# ProDocument_N64_SpyDVI_QSB_2024-08-21.net
KiCad netlist of a schematic drawn in EasyEDA Pro
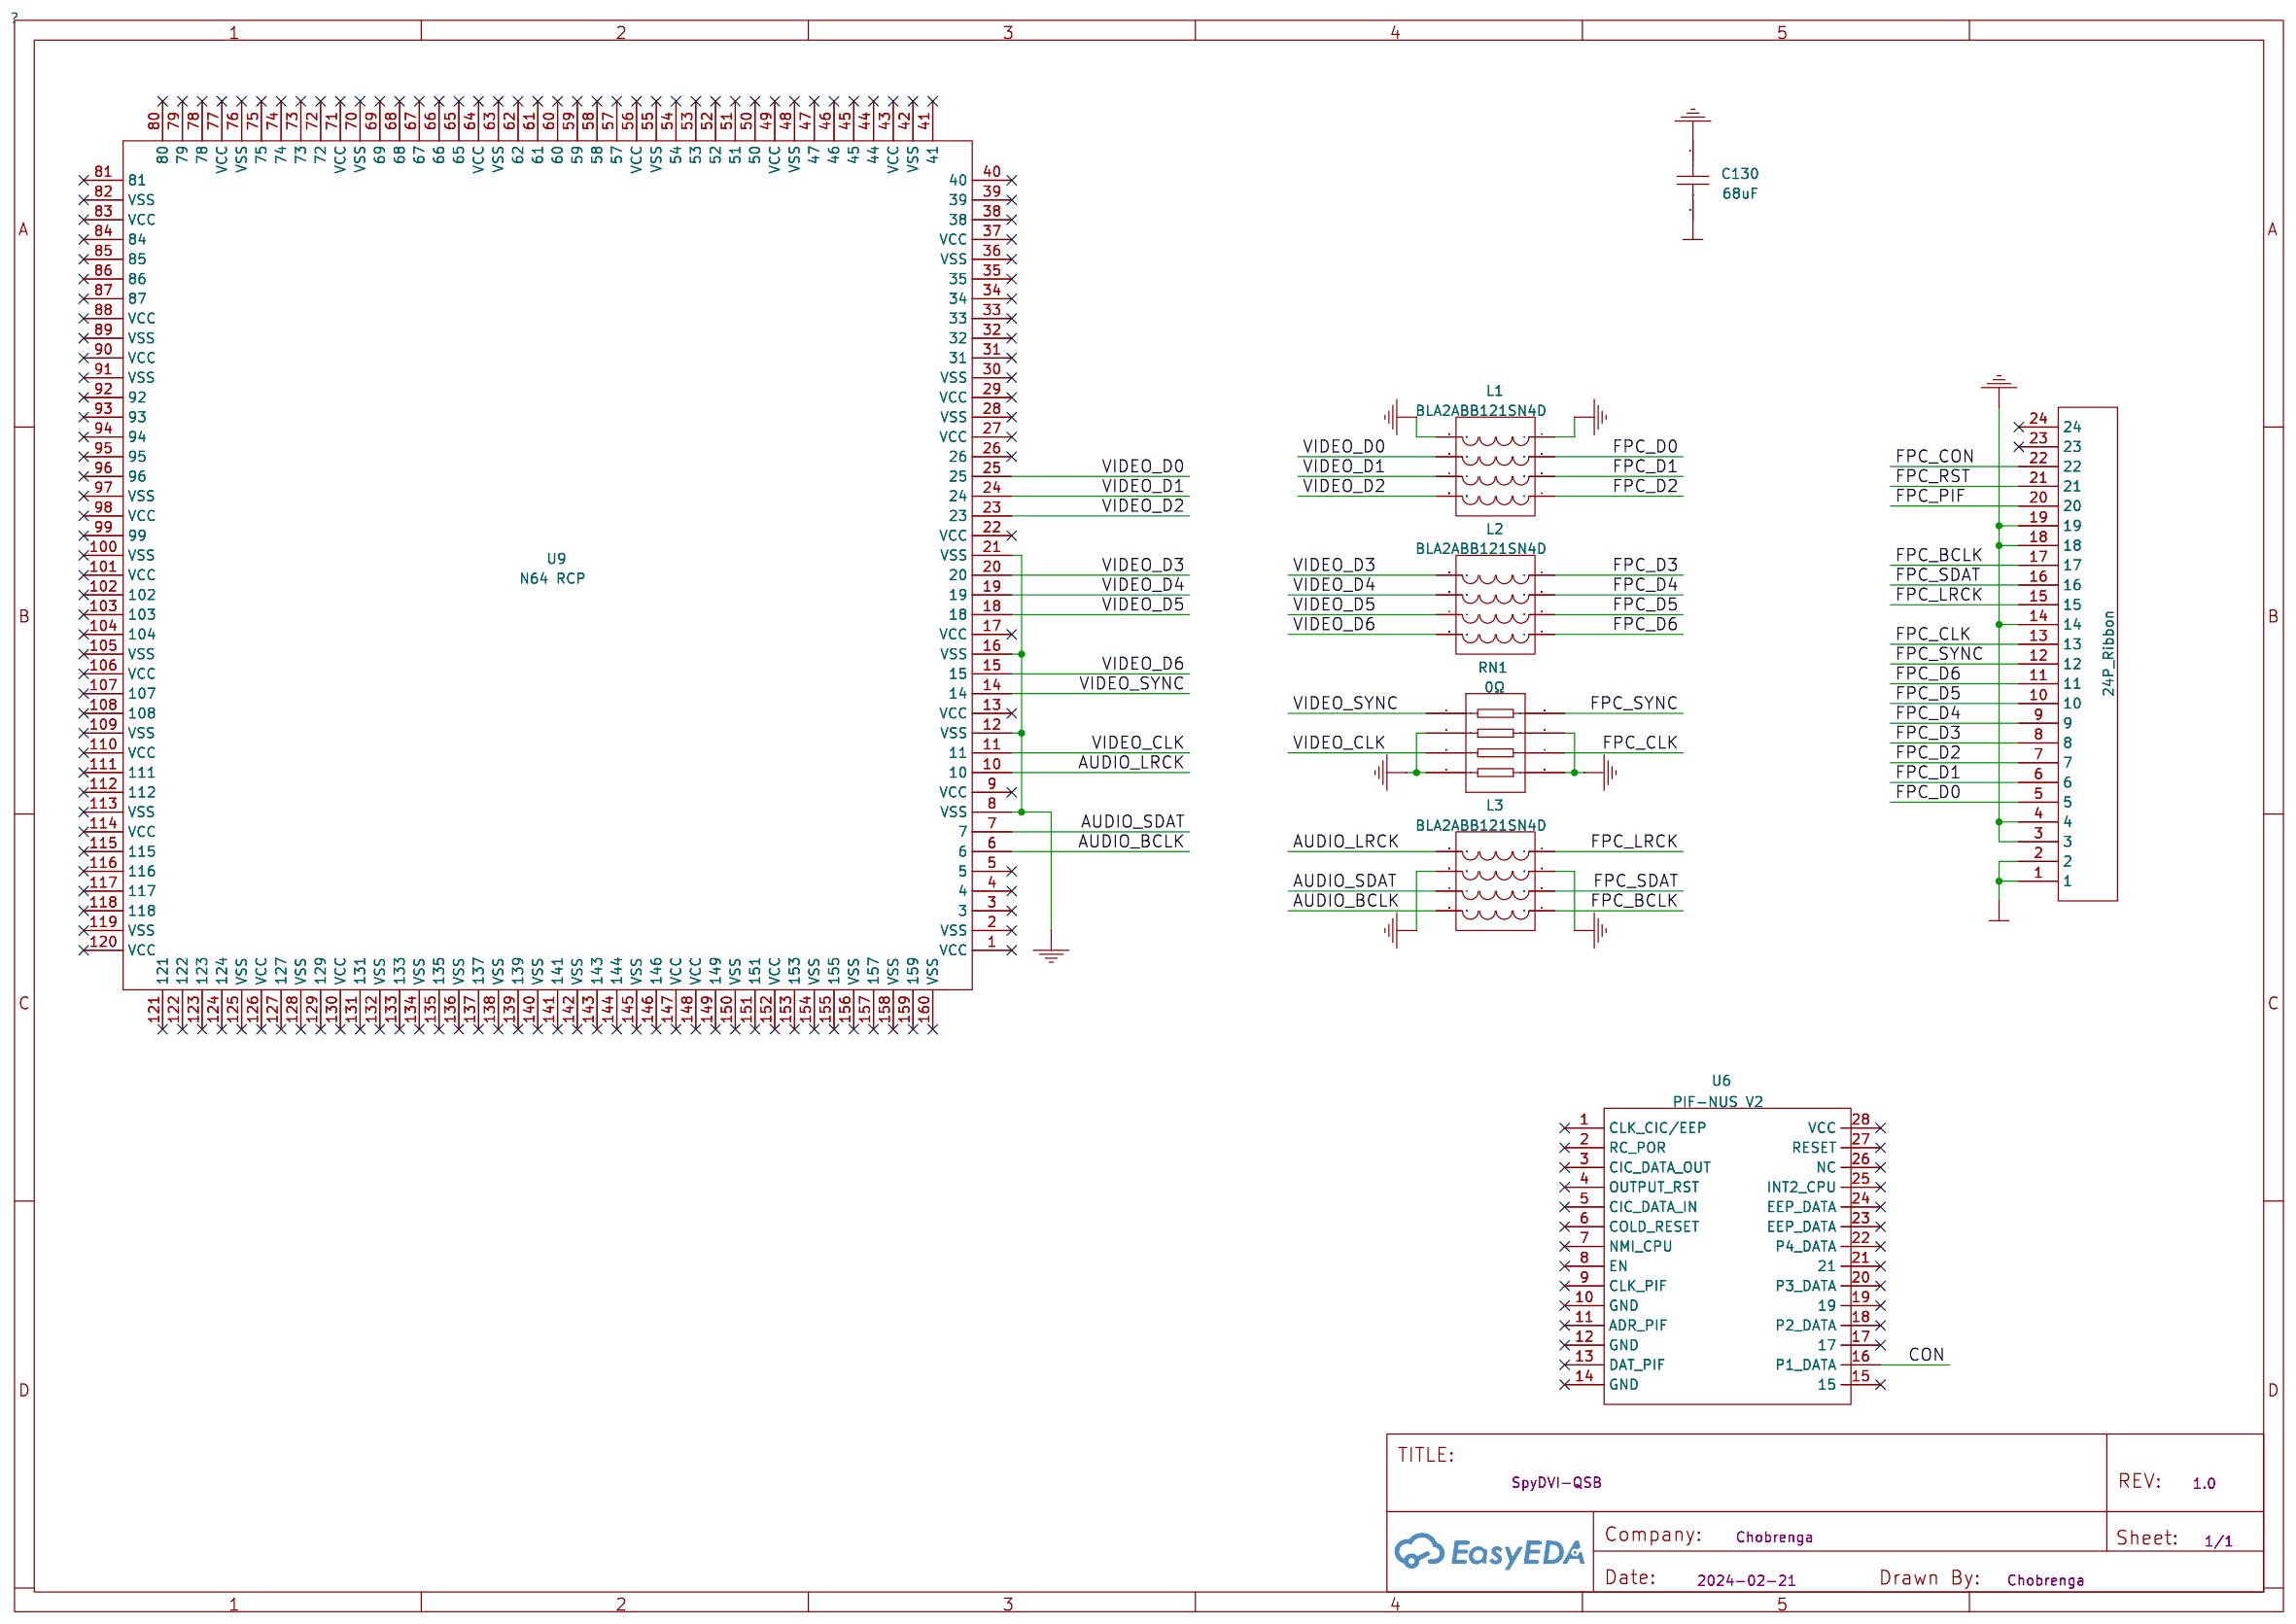
[diagram p0: schematic sheet]

(export (version "E")
  (design (tool "Eeschema 10.0.6"))
  (components
    (comp (ref "C130") (value "68uF") (libsource (lib "easyedapro") (part "68uF")))
    (comp (ref "L1")
      (value "BLA2ABB121SN4D")
      (footprint "easyedapro:BEAD-SMD_8P-L2.0-W1.0-P0.50-TL")
      (fields (field (name "Manufacturer") "muRata(村田)"))
      (libsource (lib "easyedapro") (part "BLA2ABB121SN4D"))
    )
    (comp (ref "L2")
      (value "BLA2ABB121SN4D")
      (footprint "easyedapro:BEAD-SMD_8P-L2.0-W1.0-P0.50-TL")
      (fields (field (name "Manufacturer") "muRata(村田)"))
      (libsource (lib "easyedapro") (part "BLA2ABB121SN4D"))
    )
    (comp (ref "L3")
      (value "BLA2ABB121SN4D")
      (footprint "easyedapro:BEAD-SMD_8P-L2.0-W1.0-P0.50-TL")
      (fields (field (name "Manufacturer") "muRata(村田)"))
      (libsource (lib "easyedapro") (part "BLA2ABB121SN4D"))
    )
    (comp (ref "RN1")
      (value "0Ω")
      (footprint "easyedapro:RES-ARRAY-SMD_0402-8P-L2.0-W1.0-BL")
      (fields (field (name "Manufacturer Part") "RC-MT08W000JT") (field (name "Manufacturer") "FH(风华)"))
      (libsource (lib "easyedapro") (part "0Ω"))
    )
    (comp (ref "U1")
      (value "24P_Ribbon")
      (footprint "easyedapro:24P_FFC")
      (libsource (lib "easyedapro") (part "24P_Ribbon"))
    )
    (comp (ref "U6") (value "PIF-NUS V2") (libsource (lib "easyedapro") (part "PIF-NUS V2")))
    (comp (ref "U9")
      (value "N64 RCP")
      (footprint "easyedapro:RCP NUS")
      (libsource (lib "easyedapro") (part "N64 RCP"))
    )
  )
  (nets
    (net (code "1") (name "+5V") (class "Default")
      (node (ref "C130") (pin "2") (pinfunction "2_2") (pintype "unspecified"))
      (node (ref "U1") (pin "1") (pinfunction "1_1") (pintype "unspecified"))
      (node (ref "U1") (pin "2") (pinfunction "2_2") (pintype "unspecified"))
    )
    (net (code "2") (name "/AUDIO_BCLK") (class "Default")
      (node (ref "L3") (pin "8") (pinfunction "8_8") (pintype "unspecified"))
      (node (ref "U9") (pin "6") (pinfunction "6_6") (pintype "unspecified"))
    )
    (net (code "3") (name "/AUDIO_LRCK") (class "Default")
      (node (ref "L3") (pin "5") (pinfunction "5_5") (pintype "unspecified"))
      (node (ref "U9") (pin "10") (pinfunction "10_10") (pintype "unspecified"))
    )
    (net (code "4") (name "/AUDIO_SDAT") (class "Default")
      (node (ref "L3") (pin "7") (pinfunction "7_7") (pintype "unspecified"))
      (node (ref "U9") (pin "7") (pinfunction "7_7") (pintype "unspecified"))
    )
    (net (code "5") (name "/CON") (class "Default")
      (node (ref "U6") (pin "16") (pinfunction "P1_DATA_16") (pintype "unspecified"))
    )
    (net (code "6") (name "/FPC_BCLK") (class "Default")
      (node (ref "L3") (pin "1") (pinfunction "1_1") (pintype "unspecified"))
      (node (ref "U1") (pin "17") (pinfunction "17_17") (pintype "unspecified"))
    )
    (net (code "7") (name "/FPC_CLK") (class "Default")
      (node (ref "RN1") (pin "7") (pinfunction "7_7") (pintype "input"))
      (node (ref "U1") (pin "13") (pinfunction "13_13") (pintype "unspecified"))
    )
    (net (code "8") (name "/FPC_CON") (class "Default")
      (node (ref "U1") (pin "22") (pinfunction "22_22") (pintype "unspecified"))
    )
    (net (code "9") (name "/FPC_D0") (class "Default")
      (node (ref "L1") (pin "3") (pinfunction "3_3") (pintype "unspecified"))
      (node (ref "U1") (pin "5") (pinfunction "5_5") (pintype "unspecified"))
    )
    (net (code "10") (name "/FPC_D1") (class "Default")
      (node (ref "L1") (pin "2") (pinfunction "2_2") (pintype "unspecified"))
      (node (ref "U1") (pin "6") (pinfunction "6_6") (pintype "unspecified"))
    )
    (net (code "11") (name "/FPC_D2") (class "Default")
      (node (ref "L1") (pin "1") (pinfunction "1_1") (pintype "unspecified"))
      (node (ref "U1") (pin "7") (pinfunction "7_7") (pintype "unspecified"))
    )
    (net (code "12") (name "/FPC_D3") (class "Default")
      (node (ref "L2") (pin "4") (pinfunction "4_4") (pintype "unspecified"))
      (node (ref "U1") (pin "8") (pinfunction "8_8") (pintype "unspecified"))
    )
    (net (code "13") (name "/FPC_D4") (class "Default")
      (node (ref "L2") (pin "3") (pinfunction "3_3") (pintype "unspecified"))
      (node (ref "U1") (pin "9") (pinfunction "9_9") (pintype "unspecified"))
    )
    (net (code "14") (name "/FPC_D5") (class "Default")
      (node (ref "L2") (pin "2") (pinfunction "2_2") (pintype "unspecified"))
      (node (ref "U1") (pin "10") (pinfunction "10_10") (pintype "unspecified"))
    )
    (net (code "15") (name "/FPC_D6") (class "Default")
      (node (ref "L2") (pin "1") (pinfunction "1_1") (pintype "unspecified"))
      (node (ref "U1") (pin "11") (pinfunction "11_11") (pintype "unspecified"))
    )
    (net (code "16") (name "/FPC_LRCK") (class "Default")
      (node (ref "L3") (pin "4") (pinfunction "4_4") (pintype "unspecified"))
      (node (ref "U1") (pin "15") (pinfunction "15_15") (pintype "unspecified"))
    )
    (net (code "17") (name "/FPC_PIF") (class "Default")
      (node (ref "U1") (pin "20") (pinfunction "20_20") (pintype "unspecified"))
    )
    (net (code "18") (name "/FPC_RST") (class "Default")
      (node (ref "U1") (pin "21") (pinfunction "21_21") (pintype "unspecified"))
    )
    (net (code "19") (name "/FPC_SDAT") (class "Default")
      (node (ref "L3") (pin "2") (pinfunction "2_2") (pintype "unspecified"))
      (node (ref "U1") (pin "16") (pinfunction "16_16") (pintype "unspecified"))
    )
    (net (code "20") (name "/FPC_SYNC") (class "Default")
      (node (ref "RN1") (pin "5") (pinfunction "5_5") (pintype "input"))
      (node (ref "U1") (pin "12") (pinfunction "12_12") (pintype "unspecified"))
    )
    (net (code "21") (name "/VIDEO_CLK") (class "Default")
      (node (ref "RN1") (pin "2") (pinfunction "2_2") (pintype "input"))
      (node (ref "U9") (pin "11") (pinfunction "11_11") (pintype "unspecified"))
    )
    (net (code "22") (name "/VIDEO_D0") (class "Default")
      (node (ref "L1") (pin "6") (pinfunction "6_6") (pintype "unspecified"))
      (node (ref "U9") (pin "25") (pinfunction "25_25") (pintype "unspecified"))
    )
    (net (code "23") (name "/VIDEO_D1") (class "Default")
      (node (ref "L1") (pin "7") (pinfunction "7_7") (pintype "unspecified"))
      (node (ref "U9") (pin "24") (pinfunction "24_24") (pintype "unspecified"))
    )
    (net (code "24") (name "/VIDEO_D2") (class "Default")
      (node (ref "L1") (pin "8") (pinfunction "8_8") (pintype "unspecified"))
      (node (ref "U9") (pin "23") (pinfunction "23_23") (pintype "unspecified"))
    )
    (net (code "25") (name "/VIDEO_D3") (class "Default")
      (node (ref "L2") (pin "5") (pinfunction "5_5") (pintype "unspecified"))
      (node (ref "U9") (pin "20") (pinfunction "20_20") (pintype "unspecified"))
    )
    (net (code "26") (name "/VIDEO_D4") (class "Default")
      (node (ref "L2") (pin "6") (pinfunction "6_6") (pintype "unspecified"))
      (node (ref "U9") (pin "19") (pinfunction "19_19") (pintype "unspecified"))
    )
    (net (code "27") (name "/VIDEO_D5") (class "Default")
      (node (ref "L2") (pin "7") (pinfunction "7_7") (pintype "unspecified"))
      (node (ref "U9") (pin "18") (pinfunction "18_18") (pintype "unspecified"))
    )
    (net (code "28") (name "/VIDEO_D6") (class "Default")
      (node (ref "L2") (pin "8") (pinfunction "8_8") (pintype "unspecified"))
      (node (ref "U9") (pin "15") (pinfunction "15_15") (pintype "unspecified"))
    )
    (net (code "29") (name "/VIDEO_SYNC") (class "Default")
      (node (ref "RN1") (pin "4") (pinfunction "4_4") (pintype "input"))
      (node (ref "U9") (pin "14") (pinfunction "14_14") (pintype "unspecified"))
    )
    (net (code "30") (name "GND") (class "Default")
      (node (ref "C130") (pin "1") (pinfunction "1_1") (pintype "unspecified"))
      (node (ref "L1") (pin "4") (pinfunction "4_4") (pintype "unspecified"))
      (node (ref "L1") (pin "5") (pinfunction "5_5") (pintype "unspecified"))
      (node (ref "L3") (pin "3") (pinfunction "3_3") (pintype "unspecified"))
      (node (ref "L3") (pin "6") (pinfunction "6_6") (pintype "unspecified"))
      (node (ref "RN1") (pin "1") (pinfunction "1_1") (pintype "input"))
      (node (ref "RN1") (pin "3") (pinfunction "3_3") (pintype "input"))
      (node (ref "RN1") (pin "6") (pinfunction "6_6") (pintype "input"))
      (node (ref "RN1") (pin "8") (pinfunction "8_8") (pintype "input"))
      (node (ref "U1") (pin "14") (pinfunction "14_14") (pintype "unspecified"))
      (node (ref "U1") (pin "18") (pinfunction "18_18") (pintype "unspecified"))
      (node (ref "U1") (pin "19") (pinfunction "19_19") (pintype "unspecified"))
      (node (ref "U1") (pin "3") (pinfunction "3_3") (pintype "unspecified"))
      (node (ref "U1") (pin "4") (pinfunction "4_4") (pintype "unspecified"))
      (node (ref "U9") (pin "12") (pinfunction "VSS_12") (pintype "unspecified"))
      (node (ref "U9") (pin "16") (pinfunction "VSS_16") (pintype "unspecified"))
      (node (ref "U9") (pin "21") (pinfunction "VSS_21") (pintype "unspecified"))
      (node (ref "U9") (pin "8") (pinfunction "VSS_8") (pintype "unspecified"))
    )
    (net (code "31") (name "unconnected-(U1-Pad23)") (class "Default")
      (node (ref "U1") (pin "23") (pinfunction "23_23") (pintype "unspecified+no_connect"))
    )
    (net (code "32") (name "unconnected-(U1-Pad24)") (class "Default")
      (node (ref "U1") (pin "24") (pinfunction "24_24") (pintype "unspecified+no_connect"))
    )
    (net (code "33") (name "unconnected-(U6-ADR_PIF-Pad11)") (class "Default")
      (node (ref "U6") (pin "11") (pinfunction "ADR_PIF_11") (pintype "unspecified+no_connect"))
    )
    (net (code "34") (name "unconnected-(U6-CIC_DATA_IN-Pad5)") (class "Default")
      (node (ref "U6") (pin "5") (pinfunction "CIC_DATA_IN_5") (pintype "unspecified+no_connect"))
    )
    (net (code "35") (name "unconnected-(U6-CIC_DATA_OUT-Pad3)") (class "Default")
      (node (ref "U6") (pin "3") (pinfunction "CIC_DATA_OUT_3") (pintype "unspecified+no_connect"))
    )
    (net (code "36") (name "unconnected-(U6-CLK_CIC{slash}EEP-Pad1)") (class "Default")
      (node (ref "U6") (pin "1") (pinfunction "CLK_CIC/EEP_1") (pintype "unspecified+no_connect"))
    )
    (net (code "37") (name "unconnected-(U6-CLK_PIF-Pad9)") (class "Default")
      (node (ref "U6") (pin "9") (pinfunction "CLK_PIF_9") (pintype "unspecified+no_connect"))
    )
    (net (code "38") (name "unconnected-(U6-COLD_RESET-Pad6)") (class "Default")
      (node (ref "U6") (pin "6") (pinfunction "COLD_RESET_6") (pintype "unspecified+no_connect"))
    )
    (net (code "39") (name "unconnected-(U6-DAT_PIF-Pad13)") (class "Default")
      (node (ref "U6") (pin "13") (pinfunction "DAT_PIF_13") (pintype "unspecified+no_connect"))
    )
    (net (code "40") (name "unconnected-(U6-EEP_DATA-Pad23)") (class "Default")
      (node (ref "U6") (pin "23") (pinfunction "EEP_DATA_23") (pintype "unspecified+no_connect"))
    )
    (net (code "41") (name "unconnected-(U6-EEP_DATA-Pad24)") (class "Default")
      (node (ref "U6") (pin "24") (pinfunction "EEP_DATA_24") (pintype "unspecified+no_connect"))
    )
    (net (code "42") (name "unconnected-(U6-EN-Pad8)") (class "Default")
      (node (ref "U6") (pin "8") (pinfunction "EN_8") (pintype "unspecified+no_connect"))
    )
    (net (code "43") (name "unconnected-(U6-GND-Pad10)") (class "Default")
      (node (ref "U6") (pin "10") (pinfunction "GND_10") (pintype "unspecified+no_connect"))
    )
    (net (code "44") (name "unconnected-(U6-GND-Pad12)") (class "Default")
      (node (ref "U6") (pin "12") (pinfunction "GND_12") (pintype "unspecified+no_connect"))
    )
    (net (code "45") (name "unconnected-(U6-GND-Pad14)") (class "Default")
      (node (ref "U6") (pin "14") (pinfunction "GND_14") (pintype "unspecified+no_connect"))
    )
    (net (code "46") (name "unconnected-(U6-INT2_CPU-Pad25)") (class "Default")
      (node (ref "U6") (pin "25") (pinfunction "INT2_CPU_25") (pintype "unspecified+no_connect"))
    )
    (net (code "47") (name "unconnected-(U6-NC-Pad26)") (class "Default")
      (node (ref "U6") (pin "26") (pinfunction "NC_26") (pintype "unspecified+no_connect"))
    )
    (net (code "48") (name "unconnected-(U6-NMI_CPU-Pad7)") (class "Default")
      (node (ref "U6") (pin "7") (pinfunction "NMI_CPU_7") (pintype "unspecified+no_connect"))
    )
    (net (code "49") (name "unconnected-(U6-OUTPUT_RST-Pad4)") (class "Default")
      (node (ref "U6") (pin "4") (pinfunction "OUTPUT_RST_4") (pintype "unspecified+no_connect"))
    )
    (net (code "50") (name "unconnected-(U6-P2_DATA-Pad18)") (class "Default")
      (node (ref "U6") (pin "18") (pinfunction "P2_DATA_18") (pintype "unspecified+no_connect"))
    )
    (net (code "51") (name "unconnected-(U6-P3_DATA-Pad20)") (class "Default")
      (node (ref "U6") (pin "20") (pinfunction "P3_DATA_20") (pintype "unspecified+no_connect"))
    )
    (net (code "52") (name "unconnected-(U6-P4_DATA-Pad22)") (class "Default")
      (node (ref "U6") (pin "22") (pinfunction "P4_DATA_22") (pintype "unspecified+no_connect"))
    )
    (net (code "53") (name "unconnected-(U6-Pad15)") (class "Default")
      (node (ref "U6") (pin "15") (pinfunction "15_15") (pintype "unspecified+no_connect"))
    )
    (net (code "54") (name "unconnected-(U6-Pad17)") (class "Default")
      (node (ref "U6") (pin "17") (pinfunction "17_17") (pintype "unspecified+no_connect"))
    )
    (net (code "55") (name "unconnected-(U6-Pad19)") (class "Default")
      (node (ref "U6") (pin "19") (pinfunction "19_19") (pintype "unspecified+no_connect"))
    )
    (net (code "56") (name "unconnected-(U6-Pad21)") (class "Default")
      (node (ref "U6") (pin "21") (pinfunction "21_21") (pintype "unspecified+no_connect"))
    )
    (net (code "57") (name "unconnected-(U6-RC_POR-Pad2)") (class "Default")
      (node (ref "U6") (pin "2") (pinfunction "RC_POR_2") (pintype "unspecified+no_connect"))
    )
    (net (code "58") (name "unconnected-(U6-RESET-Pad27)") (class "Default")
      (node (ref "U6") (pin "27") (pinfunction "RESET_27") (pintype "unspecified+no_connect"))
    )
    (net (code "59") (name "unconnected-(U6-VCC-Pad28)") (class "Default")
      (node (ref "U6") (pin "28") (pinfunction "VCC_28") (pintype "unspecified+no_connect"))
    )
    (net (code "60") (name "unconnected-(U9-Pad3)") (class "Default")
      (node (ref "U9") (pin "3") (pinfunction "3_3") (pintype "unspecified+no_connect"))
    )
    (net (code "61") (name "unconnected-(U9-Pad4)") (class "Default")
      (node (ref "U9") (pin "4") (pinfunction "4_4") (pintype "unspecified+no_connect"))
    )
    (net (code "62") (name "unconnected-(U9-Pad5)") (class "Default")
      (node (ref "U9") (pin "5") (pinfunction "5_5") (pintype "unspecified+no_connect"))
    )
    (net (code "63") (name "unconnected-(U9-Pad26)") (class "Default")
      (node (ref "U9") (pin "26") (pinfunction "26_26") (pintype "unspecified+no_connect"))
    )
    (net (code "64") (name "unconnected-(U9-Pad31)") (class "Default")
      (node (ref "U9") (pin "31") (pinfunction "31_31") (pintype "unspecified+no_connect"))
    )
    (net (code "65") (name "unconnected-(U9-Pad32)") (class "Default")
      (node (ref "U9") (pin "32") (pinfunction "32_32") (pintype "unspecified+no_connect"))
    )
    (net (code "66") (name "unconnected-(U9-Pad33)") (class "Default")
      (node (ref "U9") (pin "33") (pinfunction "33_33") (pintype "unspecified+no_connect"))
    )
    (net (code "67") (name "unconnected-(U9-Pad34)") (class "Default")
      (node (ref "U9") (pin "34") (pinfunction "34_34") (pintype "unspecified+no_connect"))
    )
    (net (code "68") (name "unconnected-(U9-Pad35)") (class "Default")
      (node (ref "U9") (pin "35") (pinfunction "35_35") (pintype "unspecified+no_connect"))
    )
    (net (code "69") (name "unconnected-(U9-Pad38)") (class "Default")
      (node (ref "U9") (pin "38") (pinfunction "38_38") (pintype "unspecified+no_connect"))
    )
    (net (code "70") (name "unconnected-(U9-Pad39)") (class "Default")
      (node (ref "U9") (pin "39") (pinfunction "39_39") (pintype "unspecified+no_connect"))
    )
    (net (code "71") (name "unconnected-(U9-Pad40)") (class "Default")
      (node (ref "U9") (pin "40") (pinfunction "40_40") (pintype "unspecified+no_connect"))
    )
    (net (code "72") (name "unconnected-(U9-Pad41)") (class "Default")
      (node (ref "U9") (pin "41") (pinfunction "41_41") (pintype "unspecified+no_connect"))
    )
    (net (code "73") (name "unconnected-(U9-Pad44)") (class "Default")
      (node (ref "U9") (pin "44") (pinfunction "44_44") (pintype "unspecified+no_connect"))
    )
    (net (code "74") (name "unconnected-(U9-Pad45)") (class "Default")
      (node (ref "U9") (pin "45") (pinfunction "45_45") (pintype "unspecified+no_connect"))
    )
    (net (code "75") (name "unconnected-(U9-Pad46)") (class "Default")
      (node (ref "U9") (pin "46") (pinfunction "46_46") (pintype "unspecified+no_connect"))
    )
    (net (code "76") (name "unconnected-(U9-Pad47)") (class "Default")
      (node (ref "U9") (pin "47") (pinfunction "47_47") (pintype "unspecified+no_connect"))
    )
    (net (code "77") (name "unconnected-(U9-Pad50)") (class "Default")
      (node (ref "U9") (pin "50") (pinfunction "50_50") (pintype "unspecified+no_connect"))
    )
    (net (code "78") (name "unconnected-(U9-Pad51)") (class "Default")
      (node (ref "U9") (pin "51") (pinfunction "51_51") (pintype "unspecified+no_connect"))
    )
    (net (code "79") (name "unconnected-(U9-Pad52)") (class "Default")
      (node (ref "U9") (pin "52") (pinfunction "52_52") (pintype "unspecified+no_connect"))
    )
    (net (code "80") (name "unconnected-(U9-Pad53)") (class "Default")
      (node (ref "U9") (pin "53") (pinfunction "53_53") (pintype "unspecified+no_connect"))
    )
    (net (code "81") (name "unconnected-(U9-Pad54)") (class "Default")
      (node (ref "U9") (pin "54") (pinfunction "54_54") (pintype "unspecified+no_connect"))
    )
    (net (code "82") (name "unconnected-(U9-Pad57)") (class "Default")
      (node (ref "U9") (pin "57") (pinfunction "57_57") (pintype "unspecified+no_connect"))
    )
    (net (code "83") (name "unconnected-(U9-Pad58)") (class "Default")
      (node (ref "U9") (pin "58") (pinfunction "58_58") (pintype "unspecified+no_connect"))
    )
    (net (code "84") (name "unconnected-(U9-Pad59)") (class "Default")
      (node (ref "U9") (pin "59") (pinfunction "59_59") (pintype "unspecified+no_connect"))
    )
    (net (code "85") (name "unconnected-(U9-Pad60)") (class "Default")
      (node (ref "U9") (pin "60") (pinfunction "60_60") (pintype "unspecified+no_connect"))
    )
    (net (code "86") (name "unconnected-(U9-Pad61)") (class "Default")
      (node (ref "U9") (pin "61") (pinfunction "61_61") (pintype "unspecified+no_connect"))
    )
    (net (code "87") (name "unconnected-(U9-Pad62)") (class "Default")
      (node (ref "U9") (pin "62") (pinfunction "62_62") (pintype "unspecified+no_connect"))
    )
    (net (code "88") (name "unconnected-(U9-Pad65)") (class "Default")
      (node (ref "U9") (pin "65") (pinfunction "65_65") (pintype "unspecified+no_connect"))
    )
    (net (code "89") (name "unconnected-(U9-Pad66)") (class "Default")
      (node (ref "U9") (pin "66") (pinfunction "66_66") (pintype "unspecified+no_connect"))
    )
    (net (code "90") (name "unconnected-(U9-Pad67)") (class "Default")
      (node (ref "U9") (pin "67") (pinfunction "67_67") (pintype "unspecified+no_connect"))
    )
    (net (code "91") (name "unconnected-(U9-Pad68)") (class "Default")
      (node (ref "U9") (pin "68") (pinfunction "68_68") (pintype "unspecified+no_connect"))
    )
    (net (code "92") (name "unconnected-(U9-Pad69)") (class "Default")
      (node (ref "U9") (pin "69") (pinfunction "69_69") (pintype "unspecified+no_connect"))
    )
    (net (code "93") (name "unconnected-(U9-Pad72)") (class "Default")
      (node (ref "U9") (pin "72") (pinfunction "72_72") (pintype "unspecified+no_connect"))
    )
    (net (code "94") (name "unconnected-(U9-Pad73)") (class "Default")
      (node (ref "U9") (pin "73") (pinfunction "73_73") (pintype "unspecified+no_connect"))
    )
    (net (code "95") (name "unconnected-(U9-Pad74)") (class "Default")
      (node (ref "U9") (pin "74") (pinfunction "74_74") (pintype "unspecified+no_connect"))
    )
    (net (code "96") (name "unconnected-(U9-Pad75)") (class "Default")
      (node (ref "U9") (pin "75") (pinfunction "75_75") (pintype "unspecified+no_connect"))
    )
    (net (code "97") (name "unconnected-(U9-Pad78)") (class "Default")
      (node (ref "U9") (pin "78") (pinfunction "78_78") (pintype "unspecified+no_connect"))
    )
    (net (code "98") (name "unconnected-(U9-Pad79)") (class "Default")
      (node (ref "U9") (pin "79") (pinfunction "79_79") (pintype "unspecified+no_connect"))
    )
    (net (code "99") (name "unconnected-(U9-Pad80)") (class "Default")
      (node (ref "U9") (pin "80") (pinfunction "80_80") (pintype "unspecified+no_connect"))
    )
    (net (code "100") (name "unconnected-(U9-Pad81)") (class "Default")
      (node (ref "U9") (pin "81") (pinfunction "81_81") (pintype "unspecified+no_connect"))
    )
    (net (code "101") (name "unconnected-(U9-Pad84)") (class "Default")
      (node (ref "U9") (pin "84") (pinfunction "84_84") (pintype "unspecified+no_connect"))
    )
    (net (code "102") (name "unconnected-(U9-Pad85)") (class "Default")
      (node (ref "U9") (pin "85") (pinfunction "85_85") (pintype "unspecified+no_connect"))
    )
    (net (code "103") (name "unconnected-(U9-Pad86)") (class "Default")
      (node (ref "U9") (pin "86") (pinfunction "86_86") (pintype "unspecified+no_connect"))
    )
    (net (code "104") (name "unconnected-(U9-Pad87)") (class "Default")
      (node (ref "U9") (pin "87") (pinfunction "87_87") (pintype "unspecified+no_connect"))
    )
    (net (code "105") (name "unconnected-(U9-Pad92)") (class "Default")
      (node (ref "U9") (pin "92") (pinfunction "92_92") (pintype "unspecified+no_connect"))
    )
    (net (code "106") (name "unconnected-(U9-Pad93)") (class "Default")
      (node (ref "U9") (pin "93") (pinfunction "93_93") (pintype "unspecified+no_connect"))
    )
    (net (code "107") (name "unconnected-(U9-Pad94)") (class "Default")
      (node (ref "U9") (pin "94") (pinfunction "94_94") (pintype "unspecified+no_connect"))
    )
    (net (code "108") (name "unconnected-(U9-Pad95)") (class "Default")
      (node (ref "U9") (pin "95") (pinfunction "95_95") (pintype "unspecified+no_connect"))
    )
    (net (code "109") (name "unconnected-(U9-Pad96)") (class "Default")
      (node (ref "U9") (pin "96") (pinfunction "96_96") (pintype "unspecified+no_connect"))
    )
    (net (code "110") (name "unconnected-(U9-Pad99)") (class "Default")
      (node (ref "U9") (pin "99") (pinfunction "99_99") (pintype "unspecified+no_connect"))
    )
    (net (code "111") (name "unconnected-(U9-Pad102)") (class "Default")
      (node (ref "U9") (pin "102") (pinfunction "102_102") (pintype "unspecified+no_connect"))
    )
    (net (code "112") (name "unconnected-(U9-Pad103)") (class "Default")
      (node (ref "U9") (pin "103") (pinfunction "103_103") (pintype "unspecified+no_connect"))
    )
    (net (code "113") (name "unconnected-(U9-Pad104)") (class "Default")
      (node (ref "U9") (pin "104") (pinfunction "104_104") (pintype "unspecified+no_connect"))
    )
    (net (code "114") (name "unconnected-(U9-Pad107)") (class "Default")
      (node (ref "U9") (pin "107") (pinfunction "107_107") (pintype "unspecified+no_connect"))
    )
    (net (code "115") (name "unconnected-(U9-Pad108)") (class "Default")
      (node (ref "U9") (pin "108") (pinfunction "108_108") (pintype "unspecified+no_connect"))
    )
    (net (code "116") (name "unconnected-(U9-Pad111)") (class "Default")
      (node (ref "U9") (pin "111") (pinfunction "111_111") (pintype "unspecified+no_connect"))
    )
    (net (code "117") (name "unconnected-(U9-Pad112)") (class "Default")
      (node (ref "U9") (pin "112") (pinfunction "112_112") (pintype "unspecified+no_connect"))
    )
    (net (code "118") (name "unconnected-(U9-Pad115)") (class "Default")
      (node (ref "U9") (pin "115") (pinfunction "115_115") (pintype "unspecified+no_connect"))
    )
    (net (code "119") (name "unconnected-(U9-Pad116)") (class "Default")
      (node (ref "U9") (pin "116") (pinfunction "116_116") (pintype "unspecified+no_connect"))
    )
    (net (code "120") (name "unconnected-(U9-Pad117)") (class "Default")
      (node (ref "U9") (pin "117") (pinfunction "117_117") (pintype "unspecified+no_connect"))
    )
    (net (code "121") (name "unconnected-(U9-Pad118)") (class "Default")
      (node (ref "U9") (pin "118") (pinfunction "118_118") (pintype "unspecified+no_connect"))
    )
    (net (code "122") (name "unconnected-(U9-Pad121)") (class "Default")
      (node (ref "U9") (pin "121") (pinfunction "121_121") (pintype "unspecified+no_connect"))
    )
    (net (code "123") (name "unconnected-(U9-Pad122)") (class "Default")
      (node (ref "U9") (pin "122") (pinfunction "122_122") (pintype "unspecified+no_connect"))
    )
    (net (code "124") (name "unconnected-(U9-Pad123)") (class "Default")
      (node (ref "U9") (pin "123") (pinfunction "123_123") (pintype "unspecified+no_connect"))
    )
    (net (code "125") (name "unconnected-(U9-Pad124)") (class "Default")
      (node (ref "U9") (pin "124") (pinfunction "124_124") (pintype "unspecified+no_connect"))
    )
    (net (code "126") (name "unconnected-(U9-Pad127)") (class "Default")
      (node (ref "U9") (pin "127") (pinfunction "127_127") (pintype "unspecified+no_connect"))
    )
    (net (code "127") (name "unconnected-(U9-Pad129)") (class "Default")
      (node (ref "U9") (pin "129") (pinfunction "129_129") (pintype "unspecified+no_connect"))
    )
    (net (code "128") (name "unconnected-(U9-Pad131)") (class "Default")
      (node (ref "U9") (pin "131") (pinfunction "131_131") (pintype "unspecified+no_connect"))
    )
    (net (code "129") (name "unconnected-(U9-Pad133)") (class "Default")
      (node (ref "U9") (pin "133") (pinfunction "133_133") (pintype "unspecified+no_connect"))
    )
    (net (code "130") (name "unconnected-(U9-Pad135)") (class "Default")
      (node (ref "U9") (pin "135") (pinfunction "135_135") (pintype "unspecified+no_connect"))
    )
    (net (code "131") (name "unconnected-(U9-Pad137)") (class "Default")
      (node (ref "U9") (pin "137") (pinfunction "137_137") (pintype "unspecified+no_connect"))
    )
    (net (code "132") (name "unconnected-(U9-Pad139)") (class "Default")
      (node (ref "U9") (pin "139") (pinfunction "139_139") (pintype "unspecified+no_connect"))
    )
    (net (code "133") (name "unconnected-(U9-Pad141)") (class "Default")
      (node (ref "U9") (pin "141") (pinfunction "141_141") (pintype "unspecified+no_connect"))
    )
    (net (code "134") (name "unconnected-(U9-Pad143)") (class "Default")
      (node (ref "U9") (pin "143") (pinfunction "143_143") (pintype "unspecified+no_connect"))
    )
    (net (code "135") (name "unconnected-(U9-Pad144)") (class "Default")
      (node (ref "U9") (pin "144") (pinfunction "144_144") (pintype "unspecified+no_connect"))
    )
    (net (code "136") (name "unconnected-(U9-Pad146)") (class "Default")
      (node (ref "U9") (pin "146") (pinfunction "146_146") (pintype "unspecified+no_connect"))
    )
    (net (code "137") (name "unconnected-(U9-Pad149)") (class "Default")
      (node (ref "U9") (pin "149") (pinfunction "149_149") (pintype "unspecified+no_connect"))
    )
    (net (code "138") (name "unconnected-(U9-Pad151)") (class "Default")
      (node (ref "U9") (pin "151") (pinfunction "151_151") (pintype "unspecified+no_connect"))
    )
    (net (code "139") (name "unconnected-(U9-Pad153)") (class "Default")
      (node (ref "U9") (pin "153") (pinfunction "153_153") (pintype "unspecified+no_connect"))
    )
    (net (code "140") (name "unconnected-(U9-Pad155)") (class "Default")
      (node (ref "U9") (pin "155") (pinfunction "155_155") (pintype "unspecified+no_connect"))
    )
    (net (code "141") (name "unconnected-(U9-Pad157)") (class "Default")
      (node (ref "U9") (pin "157") (pinfunction "157_157") (pintype "unspecified+no_connect"))
    )
    (net (code "142") (name "unconnected-(U9-Pad159)") (class "Default")
      (node (ref "U9") (pin "159") (pinfunction "159_159") (pintype "unspecified+no_connect"))
    )
    (net (code "143") (name "unconnected-(U9-VCC-Pad1)") (class "Default")
      (node (ref "U9") (pin "1") (pinfunction "VCC_1") (pintype "unspecified+no_connect"))
    )
    (net (code "144") (name "unconnected-(U9-VCC-Pad9)") (class "Default")
      (node (ref "U9") (pin "9") (pinfunction "VCC_9") (pintype "unspecified+no_connect"))
    )
    (net (code "145") (name "unconnected-(U9-VCC-Pad13)") (class "Default")
      (node (ref "U9") (pin "13") (pinfunction "VCC_13") (pintype "unspecified+no_connect"))
    )
    (net (code "146") (name "unconnected-(U9-VCC-Pad17)") (class "Default")
      (node (ref "U9") (pin "17") (pinfunction "VCC_17") (pintype "unspecified+no_connect"))
    )
    (net (code "147") (name "unconnected-(U9-VCC-Pad22)") (class "Default")
      (node (ref "U9") (pin "22") (pinfunction "VCC_22") (pintype "unspecified+no_connect"))
    )
    (net (code "148") (name "unconnected-(U9-VCC-Pad27)") (class "Default")
      (node (ref "U9") (pin "27") (pinfunction "VCC_27") (pintype "unspecified+no_connect"))
    )
    (net (code "149") (name "unconnected-(U9-VCC-Pad29)") (class "Default")
      (node (ref "U9") (pin "29") (pinfunction "VCC_29") (pintype "unspecified+no_connect"))
    )
    (net (code "150") (name "unconnected-(U9-VCC-Pad37)") (class "Default")
      (node (ref "U9") (pin "37") (pinfunction "VCC_37") (pintype "unspecified+no_connect"))
    )
    (net (code "151") (name "unconnected-(U9-VCC-Pad43)") (class "Default")
      (node (ref "U9") (pin "43") (pinfunction "VCC_43") (pintype "unspecified+no_connect"))
    )
    (net (code "152") (name "unconnected-(U9-VCC-Pad49)") (class "Default")
      (node (ref "U9") (pin "49") (pinfunction "VCC_49") (pintype "unspecified+no_connect"))
    )
    (net (code "153") (name "unconnected-(U9-VCC-Pad56)") (class "Default")
      (node (ref "U9") (pin "56") (pinfunction "VCC_56") (pintype "unspecified+no_connect"))
    )
    (net (code "154") (name "unconnected-(U9-VCC-Pad64)") (class "Default")
      (node (ref "U9") (pin "64") (pinfunction "VCC_64") (pintype "unspecified+no_connect"))
    )
    (net (code "155") (name "unconnected-(U9-VCC-Pad71)") (class "Default")
      (node (ref "U9") (pin "71") (pinfunction "VCC_71") (pintype "unspecified+no_connect"))
    )
    (net (code "156") (name "unconnected-(U9-VCC-Pad77)") (class "Default")
      (node (ref "U9") (pin "77") (pinfunction "VCC_77") (pintype "unspecified+no_connect"))
    )
    (net (code "157") (name "unconnected-(U9-VCC-Pad83)") (class "Default")
      (node (ref "U9") (pin "83") (pinfunction "VCC_83") (pintype "unspecified+no_connect"))
    )
    (net (code "158") (name "unconnected-(U9-VCC-Pad88)") (class "Default")
      (node (ref "U9") (pin "88") (pinfunction "VCC_88") (pintype "unspecified+no_connect"))
    )
    (net (code "159") (name "unconnected-(U9-VCC-Pad90)") (class "Default")
      (node (ref "U9") (pin "90") (pinfunction "VCC_90") (pintype "unspecified+no_connect"))
    )
    (net (code "160") (name "unconnected-(U9-VCC-Pad98)") (class "Default")
      (node (ref "U9") (pin "98") (pinfunction "VCC_98") (pintype "unspecified+no_connect"))
    )
    (net (code "161") (name "unconnected-(U9-VCC-Pad101)") (class "Default")
      (node (ref "U9") (pin "101") (pinfunction "VCC_101") (pintype "unspecified+no_connect"))
    )
    (net (code "162") (name "unconnected-(U9-VCC-Pad106)") (class "Default")
      (node (ref "U9") (pin "106") (pinfunction "VCC_106") (pintype "unspecified+no_connect"))
    )
    (net (code "163") (name "unconnected-(U9-VCC-Pad110)") (class "Default")
      (node (ref "U9") (pin "110") (pinfunction "VCC_110") (pintype "unspecified+no_connect"))
    )
    (net (code "164") (name "unconnected-(U9-VCC-Pad114)") (class "Default")
      (node (ref "U9") (pin "114") (pinfunction "VCC_114") (pintype "unspecified+no_connect"))
    )
    (net (code "165") (name "unconnected-(U9-VCC-Pad120)") (class "Default")
      (node (ref "U9") (pin "120") (pinfunction "VCC_120") (pintype "unspecified+no_connect"))
    )
    (net (code "166") (name "unconnected-(U9-VCC-Pad126)") (class "Default")
      (node (ref "U9") (pin "126") (pinfunction "VCC_126") (pintype "unspecified+no_connect"))
    )
    (net (code "167") (name "unconnected-(U9-VCC-Pad130)") (class "Default")
      (node (ref "U9") (pin "130") (pinfunction "VCC_130") (pintype "unspecified+no_connect"))
    )
    (net (code "168") (name "unconnected-(U9-VCC-Pad147)") (class "Default")
      (node (ref "U9") (pin "147") (pinfunction "VCC_147") (pintype "unspecified+no_connect"))
    )
    (net (code "169") (name "unconnected-(U9-VCC-Pad148)") (class "Default")
      (node (ref "U9") (pin "148") (pinfunction "VCC_148") (pintype "unspecified+no_connect"))
    )
    (net (code "170") (name "unconnected-(U9-VCC-Pad152)") (class "Default")
      (node (ref "U9") (pin "152") (pinfunction "VCC_152") (pintype "unspecified+no_connect"))
    )
    (net (code "171") (name "unconnected-(U9-VSS-Pad2)") (class "Default")
      (node (ref "U9") (pin "2") (pinfunction "VSS_2") (pintype "unspecified+no_connect"))
    )
    (net (code "172") (name "unconnected-(U9-VSS-Pad28)") (class "Default")
      (node (ref "U9") (pin "28") (pinfunction "VSS_28") (pintype "unspecified+no_connect"))
    )
    (net (code "173") (name "unconnected-(U9-VSS-Pad30)") (class "Default")
      (node (ref "U9") (pin "30") (pinfunction "VSS_30") (pintype "unspecified+no_connect"))
    )
    (net (code "174") (name "unconnected-(U9-VSS-Pad36)") (class "Default")
      (node (ref "U9") (pin "36") (pinfunction "VSS_36") (pintype "unspecified+no_connect"))
    )
    (net (code "175") (name "unconnected-(U9-VSS-Pad42)") (class "Default")
      (node (ref "U9") (pin "42") (pinfunction "VSS_42") (pintype "unspecified+no_connect"))
    )
    (net (code "176") (name "unconnected-(U9-VSS-Pad48)") (class "Default")
      (node (ref "U9") (pin "48") (pinfunction "VSS_48") (pintype "unspecified+no_connect"))
    )
    (net (code "177") (name "unconnected-(U9-VSS-Pad55)") (class "Default")
      (node (ref "U9") (pin "55") (pinfunction "VSS_55") (pintype "unspecified+no_connect"))
    )
    (net (code "178") (name "unconnected-(U9-VSS-Pad63)") (class "Default")
      (node (ref "U9") (pin "63") (pinfunction "VSS_63") (pintype "unspecified+no_connect"))
    )
    (net (code "179") (name "unconnected-(U9-VSS-Pad70)") (class "Default")
      (node (ref "U9") (pin "70") (pinfunction "VSS_70") (pintype "unspecified+no_connect"))
    )
    (net (code "180") (name "unconnected-(U9-VSS-Pad76)") (class "Default")
      (node (ref "U9") (pin "76") (pinfunction "VSS_76") (pintype "unspecified+no_connect"))
    )
    (net (code "181") (name "unconnected-(U9-VSS-Pad82)") (class "Default")
      (node (ref "U9") (pin "82") (pinfunction "VSS_82") (pintype "unspecified+no_connect"))
    )
    (net (code "182") (name "unconnected-(U9-VSS-Pad89)") (class "Default")
      (node (ref "U9") (pin "89") (pinfunction "VSS_89") (pintype "unspecified+no_connect"))
    )
    (net (code "183") (name "unconnected-(U9-VSS-Pad91)") (class "Default")
      (node (ref "U9") (pin "91") (pinfunction "VSS_91") (pintype "unspecified+no_connect"))
    )
    (net (code "184") (name "unconnected-(U9-VSS-Pad97)") (class "Default")
      (node (ref "U9") (pin "97") (pinfunction "VSS_97") (pintype "unspecified+no_connect"))
    )
    (net (code "185") (name "unconnected-(U9-VSS-Pad100)") (class "Default")
      (node (ref "U9") (pin "100") (pinfunction "VSS_100") (pintype "unspecified+no_connect"))
    )
    (net (code "186") (name "unconnected-(U9-VSS-Pad105)") (class "Default")
      (node (ref "U9") (pin "105") (pinfunction "VSS_105") (pintype "unspecified+no_connect"))
    )
    (net (code "187") (name "unconnected-(U9-VSS-Pad109)") (class "Default")
      (node (ref "U9") (pin "109") (pinfunction "VSS_109") (pintype "unspecified+no_connect"))
    )
    (net (code "188") (name "unconnected-(U9-VSS-Pad113)") (class "Default")
      (node (ref "U9") (pin "113") (pinfunction "VSS_113") (pintype "unspecified+no_connect"))
    )
    (net (code "189") (name "unconnected-(U9-VSS-Pad119)") (class "Default")
      (node (ref "U9") (pin "119") (pinfunction "VSS_119") (pintype "unspecified+no_connect"))
    )
    (net (code "190") (name "unconnected-(U9-VSS-Pad125)") (class "Default")
      (node (ref "U9") (pin "125") (pinfunction "VSS_125") (pintype "unspecified+no_connect"))
    )
    (net (code "191") (name "unconnected-(U9-VSS-Pad128)") (class "Default")
      (node (ref "U9") (pin "128") (pinfunction "VSS_128") (pintype "unspecified+no_connect"))
    )
    (net (code "192") (name "unconnected-(U9-VSS-Pad132)") (class "Default")
      (node (ref "U9") (pin "132") (pinfunction "VSS_132") (pintype "unspecified+no_connect"))
    )
    (net (code "193") (name "unconnected-(U9-VSS-Pad134)") (class "Default")
      (node (ref "U9") (pin "134") (pinfunction "VSS_134") (pintype "unspecified+no_connect"))
    )
    (net (code "194") (name "unconnected-(U9-VSS-Pad136)") (class "Default")
      (node (ref "U9") (pin "136") (pinfunction "VSS_136") (pintype "unspecified+no_connect"))
    )
    (net (code "195") (name "unconnected-(U9-VSS-Pad138)") (class "Default")
      (node (ref "U9") (pin "138") (pinfunction "VSS_138") (pintype "unspecified+no_connect"))
    )
    (net (code "196") (name "unconnected-(U9-VSS-Pad140)") (class "Default")
      (node (ref "U9") (pin "140") (pinfunction "VSS_140") (pintype "unspecified+no_connect"))
    )
    (net (code "197") (name "unconnected-(U9-VSS-Pad142)") (class "Default")
      (node (ref "U9") (pin "142") (pinfunction "VSS_142") (pintype "unspecified+no_connect"))
    )
    (net (code "198") (name "unconnected-(U9-VSS-Pad145)") (class "Default")
      (node (ref "U9") (pin "145") (pinfunction "VSS_145") (pintype "unspecified+no_connect"))
    )
    (net (code "199") (name "unconnected-(U9-VSS-Pad150)") (class "Default")
      (node (ref "U9") (pin "150") (pinfunction "VSS_150") (pintype "unspecified+no_connect"))
    )
    (net (code "200") (name "unconnected-(U9-VSS-Pad154)") (class "Default")
      (node (ref "U9") (pin "154") (pinfunction "VSS_154") (pintype "unspecified+no_connect"))
    )
    (net (code "201") (name "unconnected-(U9-VSS-Pad156)") (class "Default")
      (node (ref "U9") (pin "156") (pinfunction "VSS_156") (pintype "unspecified+no_connect"))
    )
    (net (code "202") (name "unconnected-(U9-VSS-Pad158)") (class "Default")
      (node (ref "U9") (pin "158") (pinfunction "VSS_158") (pintype "unspecified+no_connect"))
    )
    (net (code "203") (name "unconnected-(U9-VSS-Pad160)") (class "Default")
      (node (ref "U9") (pin "160") (pinfunction "VSS_160") (pintype "unspecified+no_connect"))
    )
  )
)
